# Connectors.net
KiCad netlist of a schematic drawn in Altium Designer
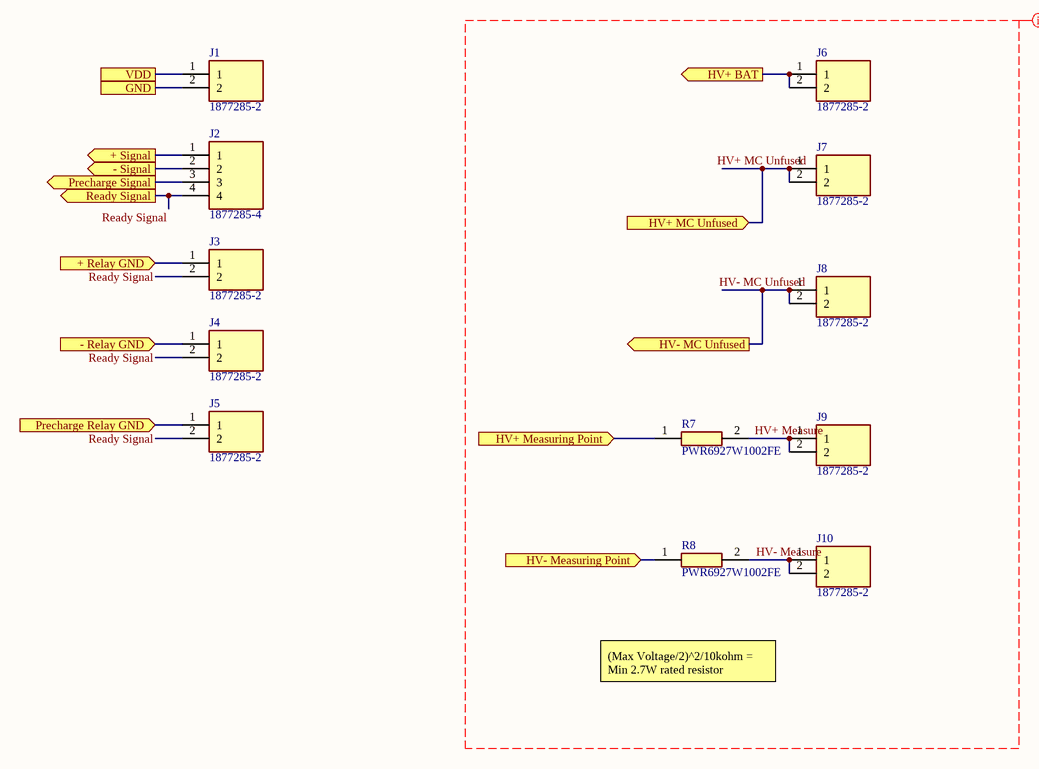
[diagram p0: Connectors.SchDoc]

(export (version "E")
  (design (tool "Eeschema 10.0.6"))
  (components
    (comp (ref "J1")
      (value "1877285-2")
      (footprint "SamacSys:18772852")
      (description "Connector")
      (fields (field (name "MOUSER PART NUMBER") "571-1877285-2"))
      (libsource (lib "*") (part "1877285-2"))
    )
    (comp (ref "J2")
      (value "1877285-4")
      (footprint "SamacSys:18772854")
      (description "Connector")
      (fields (field (name "MOUSER PART NUMBER") "571-1877285-4"))
      (libsource (lib "*") (part "1877285-4"))
    )
    (comp (ref "J3")
      (value "1877285-2")
      (footprint "SamacSys:18772852")
      (description "Connector")
      (fields (field (name "MOUSER PART NUMBER") "571-1877285-2"))
      (libsource (lib "*") (part "1877285-2"))
    )
    (comp (ref "J4")
      (value "1877285-2")
      (footprint "SamacSys:18772852")
      (description "Connector")
      (fields (field (name "MOUSER PART NUMBER") "571-1877285-2"))
      (libsource (lib "*") (part "1877285-2"))
    )
    (comp (ref "J5")
      (value "1877285-2")
      (footprint "SamacSys:18772852")
      (description "Connector")
      (fields (field (name "MOUSER PART NUMBER") "571-1877285-2"))
      (libsource (lib "*") (part "1877285-2"))
    )
    (comp (ref "J6")
      (value "1877285-2")
      (footprint "SamacSys:18772852")
      (description "Connector")
      (fields (field (name "MOUSER PART NUMBER") "571-1877285-2"))
      (libsource (lib "*") (part "1877285-2"))
    )
    (comp (ref "J7")
      (value "1877285-2")
      (footprint "SamacSys:18772852")
      (description "Connector")
      (fields (field (name "MOUSER PART NUMBER") "571-1877285-2"))
      (libsource (lib "*") (part "1877285-2"))
    )
    (comp (ref "J8")
      (value "1877285-2")
      (footprint "SamacSys:18772852")
      (description "Connector")
      (fields (field (name "MOUSER PART NUMBER") "571-1877285-2"))
      (libsource (lib "*") (part "1877285-2"))
    )
    (comp (ref "J9")
      (value "1877285-2")
      (footprint "SamacSys:18772852")
      (description "Connector")
      (fields (field (name "MOUSER PART NUMBER") "571-1877285-2"))
      (libsource (lib "*") (part "1877285-2"))
    )
    (comp (ref "J10")
      (value "1877285-2")
      (footprint "SamacSys:18772852")
      (description "Connector")
      (fields (field (name "MOUSER PART NUMBER") "571-1877285-2"))
      (libsource (lib "*") (part "1877285-2"))
    )
    (comp (ref "R7")
      (value "PWR6927W1002FE")
      (footprint "SamacSys:RESM17569X685N")
      (description "Resistor")
      (fields (field (name "MOUSER PART NUMBER") "652-PWR6927W1002FE"))
      (libsource (lib "*") (part "PWR6927W1002FE"))
    )
    (comp (ref "R8")
      (value "PWR6927W1002FE")
      (footprint "SamacSys:RESM17569X685N")
      (description "Resistor")
      (fields (field (name "MOUSER PART NUMBER") "652-PWR6927W1002FE"))
      (libsource (lib "*") (part "PWR6927W1002FE"))
    )
  )
  (nets
    (net (code "1") (name "/+ Relay GND") (class "Default")
      (node (ref "J3") (pin "1") (pinfunction "1_1") (pintype "passive"))
    )
    (net (code "2") (name "/+ Signal") (class "Default")
      (node (ref "J2") (pin "1") (pinfunction "1_1") (pintype "passive"))
    )
    (net (code "3") (name "/- Relay GND") (class "Default")
      (node (ref "J4") (pin "1") (pinfunction "1_1") (pintype "passive"))
    )
    (net (code "4") (name "/- Signal") (class "Default")
      (node (ref "J2") (pin "2") (pinfunction "2_2") (pintype "passive"))
    )
    (net (code "5") (name "/GND") (class "Default")
      (node (ref "J1") (pin "2") (pinfunction "2_2") (pintype "passive"))
    )
    (net (code "6") (name "/HV+ BAT") (class "Default")
      (node (ref "J6") (pin "1") (pinfunction "1_1") (pintype "passive"))
      (node (ref "J6") (pin "2") (pinfunction "2_2") (pintype "passive"))
    )
    (net (code "7") (name "/HV+ MC Unfused") (class "Default")
      (node (ref "J7") (pin "1") (pinfunction "1_1") (pintype "passive"))
      (node (ref "J7") (pin "2") (pinfunction "2_2") (pintype "passive"))
    )
    (net (code "8") (name "/HV+ Measure") (class "Default")
      (node (ref "J9") (pin "1") (pinfunction "1_1") (pintype "passive"))
      (node (ref "J9") (pin "2") (pinfunction "2_2") (pintype "passive"))
      (node (ref "R7") (pin "2") (pinfunction "2_2") (pintype "passive"))
    )
    (net (code "9") (name "/HV+ Measuring Point") (class "Default")
      (node (ref "R7") (pin "1") (pinfunction "1_1") (pintype "passive"))
    )
    (net (code "10") (name "/HV- MC Unfused") (class "Default")
      (node (ref "J8") (pin "1") (pinfunction "1_1") (pintype "passive"))
      (node (ref "J8") (pin "2") (pinfunction "2_2") (pintype "passive"))
    )
    (net (code "11") (name "/HV- Measure") (class "Default")
      (node (ref "J10") (pin "1") (pinfunction "1_1") (pintype "passive"))
      (node (ref "J10") (pin "2") (pinfunction "2_2") (pintype "passive"))
      (node (ref "R8") (pin "2") (pinfunction "2_2") (pintype "passive"))
    )
    (net (code "12") (name "/HV- Measuring Point") (class "Default")
      (node (ref "R8") (pin "1") (pinfunction "1_1") (pintype "passive"))
    )
    (net (code "13") (name "/Precharge Relay GND") (class "Default")
      (node (ref "J5") (pin "1") (pinfunction "1_1") (pintype "passive"))
    )
    (net (code "14") (name "/Precharge Signal") (class "Default")
      (node (ref "J2") (pin "3") (pinfunction "3_3") (pintype "passive"))
    )
    (net (code "15") (name "/Ready Signal") (class "Default")
      (node (ref "J2") (pin "4") (pinfunction "4_4") (pintype "passive"))
      (node (ref "J3") (pin "2") (pinfunction "2_2") (pintype "passive"))
      (node (ref "J4") (pin "2") (pinfunction "2_2") (pintype "passive"))
      (node (ref "J5") (pin "2") (pinfunction "2_2") (pintype "passive"))
    )
    (net (code "16") (name "/VDD") (class "Default")
      (node (ref "J1") (pin "1") (pinfunction "1_1") (pintype "passive"))
    )
  )
)
